# I2C_SW.net
KiCad netlist of a schematic drawn in Altium Designer
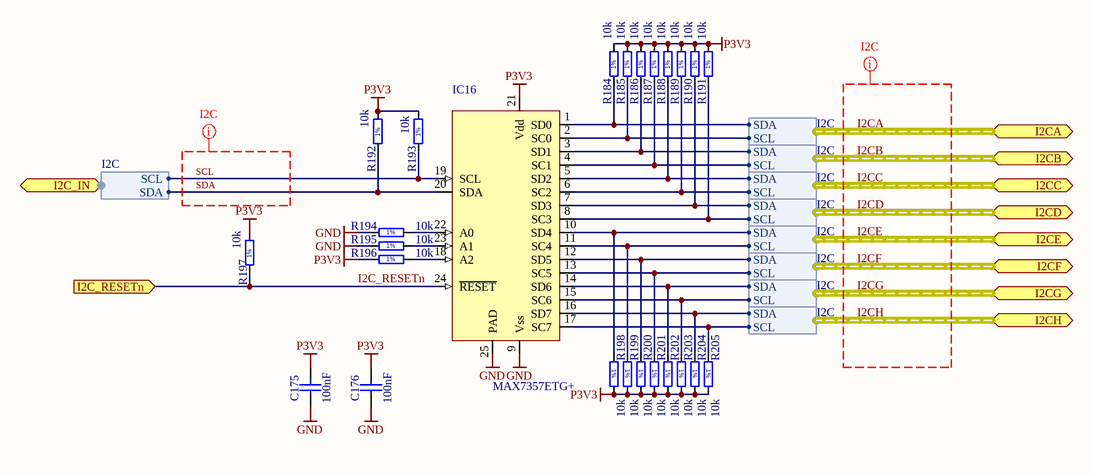
[diagram p0: I2C_SW.SchDoc]

(export (version "E")
  (design (tool "Eeschema 10.0.6"))
  (components
    (comp (ref "C175")
      (value "100nF")
      (footprint "CAPC0603X33N")
      (description "Non-polarised capacitor")
      (fields
        (field (name "PART NUMBER") "CC0201_100NF_6.3V_10%_X5R")
        (field (name "VOLTAGE") "6.3V")
        (field (name "AUTHOR") "CERN DEM JLC")
      )
      (libsource (lib "Capacitors") (part "Capacitor - non polarized"))
    )
    (comp (ref "C176")
      (value "100nF")
      (footprint "CAPC0603X33N")
      (description "Non-polarised capacitor")
      (fields
        (field (name "PART NUMBER") "CC0201_100NF_6.3V_10%_X5R")
        (field (name "VOLTAGE") "6.3V")
        (field (name "AUTHOR") "CERN DEM JLC")
      )
      (libsource (lib "Capacitors") (part "Capacitor - non polarized"))
    )
    (comp (ref "IC16")
      (value "MAX7357ETG+")
      (footprint "HVQFN24")
      (description "8-channel I2C-bus multiplexer with reset, INT and timeout")
      (libsource (lib "LIBRARY_SCH") (part "IIC_MUX_MAX7357ETG+"))
    )
    (comp (ref "R184")
      (value "10k")
      (footprint "RESC1005X40N")
      (description "Resistor - 1%")
      (fields
        (field (name "PART NUMBER") "R0402_10K_1%_0.0625W_100PPM")
        (field (name "POWER") "0.0625W")
        (field (name "AUTHOR") "CERN DEM JLC")
      )
      (libsource (lib "Resistors") (part "Resistor - 1%"))
    )
    (comp (ref "R185")
      (value "10k")
      (footprint "RESC1005X40N")
      (description "Resistor - 1%")
      (fields
        (field (name "PART NUMBER") "R0402_10K_1%_0.0625W_100PPM")
        (field (name "POWER") "0.0625W")
        (field (name "AUTHOR") "CERN DEM JLC")
      )
      (libsource (lib "Resistors") (part "Resistor - 1%"))
    )
    (comp (ref "R186")
      (value "10k")
      (footprint "RESC1005X40N")
      (description "Resistor - 1%")
      (fields
        (field (name "PART NUMBER") "R0402_10K_1%_0.0625W_100PPM")
        (field (name "POWER") "0.0625W")
        (field (name "AUTHOR") "CERN DEM JLC")
      )
      (libsource (lib "Resistors") (part "Resistor - 1%"))
    )
    (comp (ref "R187")
      (value "10k")
      (footprint "RESC1005X40N")
      (description "Resistor - 1%")
      (fields
        (field (name "PART NUMBER") "R0402_10K_1%_0.0625W_100PPM")
        (field (name "POWER") "0.0625W")
        (field (name "AUTHOR") "CERN DEM JLC")
      )
      (libsource (lib "Resistors") (part "Resistor - 1%"))
    )
    (comp (ref "R188")
      (value "10k")
      (footprint "RESC1005X40N")
      (description "Resistor - 1%")
      (fields
        (field (name "PART NUMBER") "R0402_10K_1%_0.0625W_100PPM")
        (field (name "POWER") "0.0625W")
        (field (name "AUTHOR") "CERN DEM JLC")
      )
      (libsource (lib "Resistors") (part "Resistor - 1%"))
    )
    (comp (ref "R189")
      (value "10k")
      (footprint "RESC1005X40N")
      (description "Resistor - 1%")
      (fields
        (field (name "PART NUMBER") "R0402_10K_1%_0.0625W_100PPM")
        (field (name "POWER") "0.0625W")
        (field (name "AUTHOR") "CERN DEM JLC")
      )
      (libsource (lib "Resistors") (part "Resistor - 1%"))
    )
    (comp (ref "R190")
      (value "10k")
      (footprint "RESC1005X40N")
      (description "Resistor - 1%")
      (fields
        (field (name "PART NUMBER") "R0402_10K_1%_0.0625W_100PPM")
        (field (name "POWER") "0.0625W")
        (field (name "AUTHOR") "CERN DEM JLC")
      )
      (libsource (lib "Resistors") (part "Resistor - 1%"))
    )
    (comp (ref "R191")
      (value "10k")
      (footprint "RESC1005X40N")
      (description "Resistor - 1%")
      (fields
        (field (name "PART NUMBER") "R0402_10K_1%_0.0625W_100PPM")
        (field (name "POWER") "0.0625W")
        (field (name "AUTHOR") "CERN DEM JLC")
      )
      (libsource (lib "Resistors") (part "Resistor - 1%"))
    )
    (comp (ref "R192")
      (value "10k")
      (footprint "RESC1005X40N")
      (description "Resistor - 1%")
      (fields
        (field (name "PART NUMBER") "R0402_10K_1%_0.0625W_100PPM")
        (field (name "POWER") "0.0625W")
        (field (name "AUTHOR") "CERN DEM JLC")
      )
      (libsource (lib "Resistors") (part "Resistor - 1%"))
    )
    (comp (ref "R193")
      (value "10k")
      (footprint "RESC1005X40N")
      (description "Resistor - 1%")
      (fields
        (field (name "PART NUMBER") "R0402_10K_1%_0.0625W_100PPM")
        (field (name "POWER") "0.0625W")
        (field (name "AUTHOR") "CERN DEM JLC")
      )
      (libsource (lib "Resistors") (part "Resistor - 1%"))
    )
    (comp (ref "R194")
      (value "10k")
      (footprint "RESC1005X40N")
      (description "Resistor - 1%")
      (fields
        (field (name "PART NUMBER") "R0402_10K_1%_0.0625W_100PPM")
        (field (name "POWER") "0.0625W")
        (field (name "AUTHOR") "CERN DEM JLC")
      )
      (libsource (lib "Resistors") (part "Resistor - 1%"))
    )
    (comp (ref "R195")
      (value "10k")
      (footprint "RESC1005X40N")
      (description "Resistor - 1%")
      (fields
        (field (name "PART NUMBER") "R0402_10K_1%_0.0625W_100PPM")
        (field (name "POWER") "0.0625W")
        (field (name "AUTHOR") "CERN DEM JLC")
      )
      (libsource (lib "Resistors") (part "Resistor - 1%"))
    )
    (comp (ref "R196")
      (value "10k")
      (footprint "RESC1005X40N")
      (description "Resistor - 1%")
      (fields
        (field (name "PART NUMBER") "R0402_10K_1%_0.0625W_100PPM")
        (field (name "POWER") "0.0625W")
        (field (name "AUTHOR") "CERN DEM JLC")
      )
      (libsource (lib "Resistors") (part "Resistor - 1%"))
    )
    (comp (ref "R197")
      (value "10k")
      (footprint "RESC1005X40N")
      (description "Resistor - 1%")
      (fields
        (field (name "PART NUMBER") "R0402_10K_1%_0.0625W_100PPM")
        (field (name "POWER") "0.0625W")
        (field (name "AUTHOR") "CERN DEM JLC")
      )
      (libsource (lib "Resistors") (part "Resistor - 1%"))
    )
    (comp (ref "R198")
      (value "10k")
      (footprint "RESC1005X40N")
      (description "Resistor - 1%")
      (fields
        (field (name "PART NUMBER") "R0402_10K_1%_0.0625W_100PPM")
        (field (name "POWER") "0.0625W")
        (field (name "AUTHOR") "CERN DEM JLC")
      )
      (libsource (lib "Resistors") (part "Resistor - 1%"))
    )
    (comp (ref "R199")
      (value "10k")
      (footprint "RESC1005X40N")
      (description "Resistor - 1%")
      (fields
        (field (name "PART NUMBER") "R0402_10K_1%_0.0625W_100PPM")
        (field (name "POWER") "0.0625W")
        (field (name "AUTHOR") "CERN DEM JLC")
      )
      (libsource (lib "Resistors") (part "Resistor - 1%"))
    )
    (comp (ref "R200")
      (value "10k")
      (footprint "RESC1005X40N")
      (description "Resistor - 1%")
      (fields
        (field (name "PART NUMBER") "R0402_10K_1%_0.0625W_100PPM")
        (field (name "POWER") "0.0625W")
        (field (name "AUTHOR") "CERN DEM JLC")
      )
      (libsource (lib "Resistors") (part "Resistor - 1%"))
    )
    (comp (ref "R201")
      (value "10k")
      (footprint "RESC1005X40N")
      (description "Resistor - 1%")
      (fields
        (field (name "PART NUMBER") "R0402_10K_1%_0.0625W_100PPM")
        (field (name "POWER") "0.0625W")
        (field (name "AUTHOR") "CERN DEM JLC")
      )
      (libsource (lib "Resistors") (part "Resistor - 1%"))
    )
    (comp (ref "R202")
      (value "10k")
      (footprint "RESC1005X40N")
      (description "Resistor - 1%")
      (fields
        (field (name "PART NUMBER") "R0402_10K_1%_0.0625W_100PPM")
        (field (name "POWER") "0.0625W")
        (field (name "AUTHOR") "CERN DEM JLC")
      )
      (libsource (lib "Resistors") (part "Resistor - 1%"))
    )
    (comp (ref "R203")
      (value "10k")
      (footprint "RESC1005X40N")
      (description "Resistor - 1%")
      (fields
        (field (name "PART NUMBER") "R0402_10K_1%_0.0625W_100PPM")
        (field (name "POWER") "0.0625W")
        (field (name "AUTHOR") "CERN DEM JLC")
      )
      (libsource (lib "Resistors") (part "Resistor - 1%"))
    )
    (comp (ref "R204")
      (value "10k")
      (footprint "RESC1005X40N")
      (description "Resistor - 1%")
      (fields
        (field (name "PART NUMBER") "R0402_10K_1%_0.0625W_100PPM")
        (field (name "POWER") "0.0625W")
        (field (name "AUTHOR") "CERN DEM JLC")
      )
      (libsource (lib "Resistors") (part "Resistor - 1%"))
    )
    (comp (ref "R205")
      (value "10k")
      (footprint "RESC1005X40N")
      (description "Resistor - 1%")
      (fields
        (field (name "PART NUMBER") "R0402_10K_1%_0.0625W_100PPM")
        (field (name "POWER") "0.0625W")
        (field (name "AUTHOR") "CERN DEM JLC")
      )
      (libsource (lib "Resistors") (part "Resistor - 1%"))
    )
  )
  (nets
    (net (code "18") (name "/I2C_RESETn") (class "Default")
      (node (ref "IC16") (pin "24") (pinfunction "~{RESET}_24") (pintype "input"))
      (node (ref "R197") (pin "1") (pinfunction "1_1") (pintype "passive"))
    )
    (net (code "19") (name "/SCL") (class "Default")
      (node (ref "IC16") (pin "19") (pinfunction "SCL_19") (pintype "input"))
      (node (ref "R193") (pin "1") (pinfunction "1_1") (pintype "passive"))
    )
    (net (code "20") (name "/SDA") (class "Default")
      (node (ref "IC16") (pin "20") (pinfunction "SDA_20") (pintype "bidirectional"))
      (node (ref "R192") (pin "1") (pinfunction "1_1") (pintype "passive"))
    )
    (net (code "22") (name "GND") (class "Default")
      (node (ref "C175") (pin "1") (pinfunction "1_1") (pintype "passive"))
      (node (ref "C176") (pin "1") (pinfunction "1_1") (pintype "passive"))
      (node (ref "IC16") (pin "25") (pinfunction "PAD_25") (pintype "power_in"))
      (node (ref "IC16") (pin "9") (pinfunction "Vss_9") (pintype "power_in"))
      (node (ref "R194") (pin "1") (pinfunction "1_1") (pintype "passive"))
      (node (ref "R195") (pin "1") (pinfunction "1_1") (pintype "passive"))
    )
    (net (code "23") (name "Net-(IC16-A0)") (class "Default")
      (node (ref "IC16") (pin "22") (pinfunction "A0_22") (pintype "input"))
      (node (ref "R194") (pin "2") (pinfunction "2_2") (pintype "passive"))
    )
    (net (code "24") (name "Net-(IC16-A1)") (class "Default")
      (node (ref "IC16") (pin "23") (pinfunction "A1_23") (pintype "input"))
      (node (ref "R195") (pin "2") (pinfunction "2_2") (pintype "passive"))
    )
    (net (code "25") (name "Net-(IC16-A2)") (class "Default")
      (node (ref "IC16") (pin "18") (pinfunction "A2_18") (pintype "input"))
      (node (ref "R196") (pin "2") (pinfunction "2_2") (pintype "passive"))
    )
    (net (code "26") (name "Net-(IC16-SC0)") (class "Default")
      (node (ref "IC16") (pin "2") (pinfunction "SC0_2") (pintype "bidirectional"))
      (node (ref "R185") (pin "1") (pinfunction "1_1") (pintype "passive"))
    )
    (net (code "27") (name "Net-(IC16-SC1)") (class "Default")
      (node (ref "IC16") (pin "4") (pinfunction "SC1_4") (pintype "bidirectional"))
      (node (ref "R187") (pin "1") (pinfunction "1_1") (pintype "passive"))
    )
    (net (code "28") (name "Net-(IC16-SC2)") (class "Default")
      (node (ref "IC16") (pin "6") (pinfunction "SC2_6") (pintype "bidirectional"))
      (node (ref "R189") (pin "1") (pinfunction "1_1") (pintype "passive"))
    )
    (net (code "29") (name "Net-(IC16-SC3)") (class "Default")
      (node (ref "IC16") (pin "8") (pinfunction "SC3_8") (pintype "bidirectional"))
      (node (ref "R191") (pin "1") (pinfunction "1_1") (pintype "passive"))
    )
    (net (code "30") (name "Net-(IC16-SC4)") (class "Default")
      (node (ref "IC16") (pin "11") (pinfunction "SC4_11") (pintype "bidirectional"))
      (node (ref "R199") (pin "1") (pinfunction "1_1") (pintype "passive"))
    )
    (net (code "31") (name "Net-(IC16-SC5)") (class "Default")
      (node (ref "IC16") (pin "13") (pinfunction "SC5_13") (pintype "bidirectional"))
      (node (ref "R201") (pin "1") (pinfunction "1_1") (pintype "passive"))
    )
    (net (code "32") (name "Net-(IC16-SC6)") (class "Default")
      (node (ref "IC16") (pin "15") (pinfunction "SC6_15") (pintype "bidirectional"))
      (node (ref "R203") (pin "1") (pinfunction "1_1") (pintype "passive"))
    )
    (net (code "33") (name "Net-(IC16-SC7)") (class "Default")
      (node (ref "IC16") (pin "17") (pinfunction "SC7_17") (pintype "bidirectional"))
      (node (ref "R205") (pin "1") (pinfunction "1_1") (pintype "passive"))
    )
    (net (code "34") (name "Net-(IC16-SD0)") (class "Default")
      (node (ref "IC16") (pin "1") (pinfunction "SD0_1") (pintype "bidirectional"))
      (node (ref "R184") (pin "1") (pinfunction "1_1") (pintype "passive"))
    )
    (net (code "35") (name "Net-(IC16-SD1)") (class "Default")
      (node (ref "IC16") (pin "3") (pinfunction "SD1_3") (pintype "bidirectional"))
      (node (ref "R186") (pin "1") (pinfunction "1_1") (pintype "passive"))
    )
    (net (code "36") (name "Net-(IC16-SD2)") (class "Default")
      (node (ref "IC16") (pin "5") (pinfunction "SD2_5") (pintype "bidirectional"))
      (node (ref "R188") (pin "1") (pinfunction "1_1") (pintype "passive"))
    )
    (net (code "37") (name "Net-(IC16-SD3)") (class "Default")
      (node (ref "IC16") (pin "7") (pinfunction "SD3_7") (pintype "bidirectional"))
      (node (ref "R190") (pin "1") (pinfunction "1_1") (pintype "passive"))
    )
    (net (code "38") (name "Net-(IC16-SD4)") (class "Default")
      (node (ref "IC16") (pin "10") (pinfunction "SD4_10") (pintype "bidirectional"))
      (node (ref "R198") (pin "1") (pinfunction "1_1") (pintype "passive"))
    )
    (net (code "39") (name "Net-(IC16-SD5)") (class "Default")
      (node (ref "IC16") (pin "12") (pinfunction "SD5_12") (pintype "bidirectional"))
      (node (ref "R200") (pin "1") (pinfunction "1_1") (pintype "passive"))
    )
    (net (code "40") (name "Net-(IC16-SD6)") (class "Default")
      (node (ref "IC16") (pin "14") (pinfunction "SD6_14") (pintype "bidirectional"))
      (node (ref "R202") (pin "1") (pinfunction "1_1") (pintype "passive"))
    )
    (net (code "41") (name "Net-(IC16-SD7)") (class "Default")
      (node (ref "IC16") (pin "16") (pinfunction "SD7_16") (pintype "bidirectional"))
      (node (ref "R204") (pin "1") (pinfunction "1_1") (pintype "passive"))
    )
    (net (code "42") (name "P3V3") (class "Default")
      (node (ref "C175") (pin "2") (pinfunction "2_2") (pintype "passive"))
      (node (ref "C176") (pin "2") (pinfunction "2_2") (pintype "passive"))
      (node (ref "IC16") (pin "21") (pinfunction "Vdd_21") (pintype "power_in"))
      (node (ref "R184") (pin "2") (pinfunction "2_2") (pintype "passive"))
      (node (ref "R185") (pin "2") (pinfunction "2_2") (pintype "passive"))
      (node (ref "R186") (pin "2") (pinfunction "2_2") (pintype "passive"))
      (node (ref "R187") (pin "2") (pinfunction "2_2") (pintype "passive"))
      (node (ref "R188") (pin "2") (pinfunction "2_2") (pintype "passive"))
      (node (ref "R189") (pin "2") (pinfunction "2_2") (pintype "passive"))
      (node (ref "R190") (pin "2") (pinfunction "2_2") (pintype "passive"))
      (node (ref "R191") (pin "2") (pinfunction "2_2") (pintype "passive"))
      (node (ref "R192") (pin "2") (pinfunction "2_2") (pintype "passive"))
      (node (ref "R193") (pin "2") (pinfunction "2_2") (pintype "passive"))
      (node (ref "R196") (pin "1") (pinfunction "1_1") (pintype "passive"))
      (node (ref "R197") (pin "2") (pinfunction "2_2") (pintype "passive"))
      (node (ref "R198") (pin "2") (pinfunction "2_2") (pintype "passive"))
      (node (ref "R199") (pin "2") (pinfunction "2_2") (pintype "passive"))
      (node (ref "R200") (pin "2") (pinfunction "2_2") (pintype "passive"))
      (node (ref "R201") (pin "2") (pinfunction "2_2") (pintype "passive"))
      (node (ref "R202") (pin "2") (pinfunction "2_2") (pintype "passive"))
      (node (ref "R203") (pin "2") (pinfunction "2_2") (pintype "passive"))
      (node (ref "R204") (pin "2") (pinfunction "2_2") (pintype "passive"))
      (node (ref "R205") (pin "2") (pinfunction "2_2") (pintype "passive"))
    )
  )
)
